# game_console_schematic.net
KiCad netlist of a schematic drawn in Altium Designer
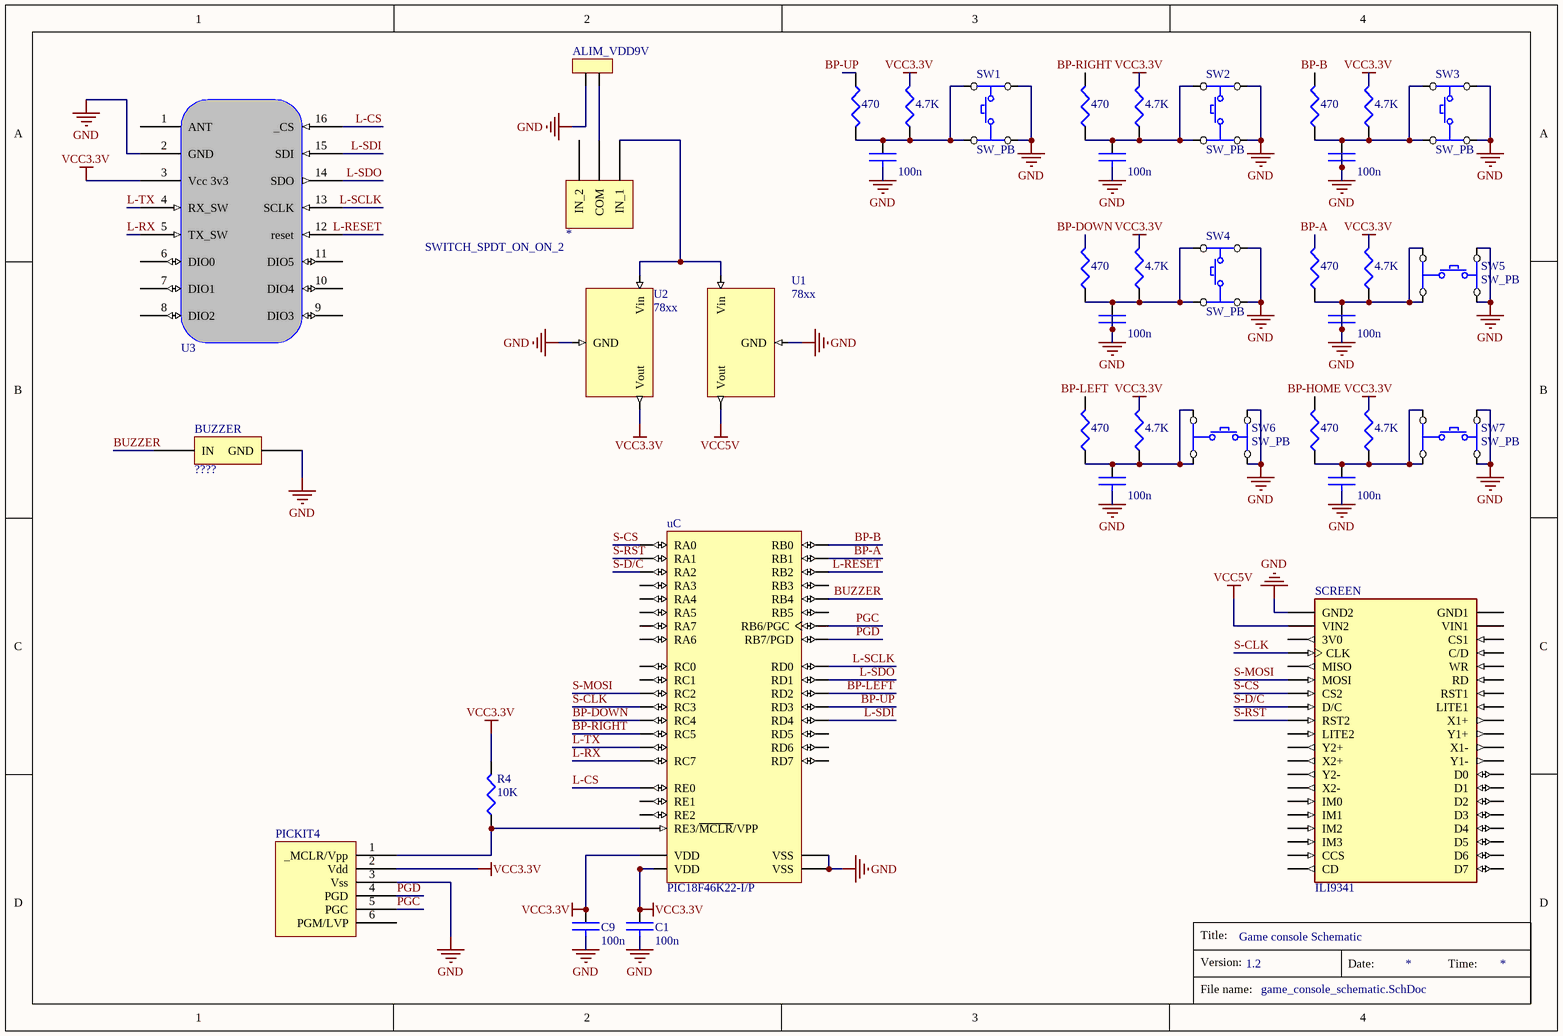
[diagram p0: game_console_schematic.SchDoc]

(export (version "E")
  (design (tool "Eeschema 10.0.6"))
  (components
    (comp (ref "*")
      (value "SWITCH_SPDT_ON_ON_2")
      (footprint "SW_MFP-161")
      (libsource (lib "ISEN_basics_15-02-2023") (part "SWITCH_SPDT_ON_ON_2"))
    )
    (comp (ref "ALIM_VDD9V")
      (value "~")
      (footprint "AMP_2")
      (description "connecteur alim 2 pôles")
      (libsource (lib "ISEN_basics_15-02-2023") (part "POWER2"))
    )
    (comp (ref "BUZZER")
      (value "????")
      (footprint "BUZZER")
      (libsource (lib "ISEN_basics_15-02-2023") (part "BUZZER"))
    )
    (comp (ref "C1")
      (value "100n")
      (footprint "0402")
      (description "capacité non polarisée")
      (fields (field (name "Comment") "CAP"))
      (libsource (lib "ISEN_basics_15-02-2023") (part "CAP"))
    )
    (comp (ref "C2")
      (value "100n")
      (footprint "0402")
      (description "capacité non polarisée")
      (fields (field (name "Comment") "CAP"))
      (libsource (lib "ISEN_basics_15-02-2023") (part "CAP"))
    )
    (comp (ref "C3")
      (value "100n")
      (footprint "0402")
      (description "capacité non polarisée")
      (fields (field (name "Comment") "CAP"))
      (libsource (lib "ISEN_basics_15-02-2023") (part "CAP"))
    )
    (comp (ref "C4")
      (value "100n")
      (footprint "0402")
      (description "capacité non polarisée")
      (fields (field (name "Comment") "CAP"))
      (libsource (lib "ISEN_basics_15-02-2023") (part "CAP"))
    )
    (comp (ref "C5")
      (value "100n")
      (footprint "0402")
      (description "capacité non polarisée")
      (fields (field (name "Comment") "CAP"))
      (libsource (lib "ISEN_basics_15-02-2023") (part "CAP"))
    )
    (comp (ref "C6")
      (value "100n")
      (footprint "0402")
      (description "capacité non polarisée")
      (fields (field (name "Comment") "CAP"))
      (libsource (lib "ISEN_basics_15-02-2023") (part "CAP"))
    )
    (comp (ref "C7")
      (value "100n")
      (footprint "0402")
      (description "capacité non polarisée")
      (fields (field (name "Comment") "CAP"))
      (libsource (lib "ISEN_basics_15-02-2023") (part "CAP"))
    )
    (comp (ref "C8")
      (value "100n")
      (footprint "0402")
      (description "capacité non polarisée")
      (fields (field (name "Comment") "CAP"))
      (libsource (lib "ISEN_basics_15-02-2023") (part "CAP"))
    )
    (comp (ref "C9")
      (value "100n")
      (footprint "0402")
      (description "capacité non polarisée")
      (fields (field (name "Comment") "CAP"))
      (libsource (lib "ISEN_basics_15-02-2023") (part "CAP"))
    )
    (comp (ref "PICKIT4")
      (value "~")
      (footprint "PIC-ICSP")
      (libsource (lib "ISEN_basics_15-02-2023") (part "PIC-ICSP"))
    )
    (comp (ref "R1")
      (value "470")
      (footprint "0201")
      (description "resistance")
      (fields (field (name "Comment") "RES"))
      (libsource (lib "ISEN_basics_15-02-2023") (part "RES"))
    )
    (comp (ref "R2")
      (value "4.7K")
      (footprint "0201")
      (description "resistance")
      (fields (field (name "Comment") "RES"))
      (libsource (lib "ISEN_basics_15-02-2023") (part "RES"))
    )
    (comp (ref "R4")
      (value "10K")
      (footprint "0201")
      (description "resistance")
      (fields (field (name "Comment") "RES"))
      (libsource (lib "ISEN_basics_15-02-2023") (part "RES"))
    )
    (comp (ref "R12")
      (value "470")
      (footprint "0201")
      (description "resistance")
      (fields (field (name "Comment") "RES"))
      (libsource (lib "ISEN_basics_15-02-2023") (part "RES"))
    )
    (comp (ref "R13")
      (value "4.7K")
      (footprint "0201")
      (description "resistance")
      (fields (field (name "Comment") "RES"))
      (libsource (lib "ISEN_basics_15-02-2023") (part "RES"))
    )
    (comp (ref "R14")
      (value "470")
      (footprint "0201")
      (description "resistance")
      (fields (field (name "Comment") "RES"))
      (libsource (lib "ISEN_basics_15-02-2023") (part "RES"))
    )
    (comp (ref "R15")
      (value "4.7K")
      (footprint "0201")
      (description "resistance")
      (fields (field (name "Comment") "RES"))
      (libsource (lib "ISEN_basics_15-02-2023") (part "RES"))
    )
    (comp (ref "R16")
      (value "470")
      (footprint "0201")
      (description "resistance")
      (fields (field (name "Comment") "RES"))
      (libsource (lib "ISEN_basics_15-02-2023") (part "RES"))
    )
    (comp (ref "R17")
      (value "4.7K")
      (footprint "0201")
      (description "resistance")
      (fields (field (name "Comment") "RES"))
      (libsource (lib "ISEN_basics_15-02-2023") (part "RES"))
    )
    (comp (ref "R18")
      (value "470")
      (footprint "0201")
      (description "resistance")
      (fields (field (name "Comment") "RES"))
      (libsource (lib "ISEN_basics_15-02-2023") (part "RES"))
    )
    (comp (ref "R19")
      (value "4.7K")
      (footprint "0201")
      (description "resistance")
      (fields (field (name "Comment") "RES"))
      (libsource (lib "ISEN_basics_15-02-2023") (part "RES"))
    )
    (comp (ref "R20")
      (value "470")
      (footprint "0201")
      (description "resistance")
      (fields (field (name "Comment") "RES"))
      (libsource (lib "ISEN_basics_15-02-2023") (part "RES"))
    )
    (comp (ref "R21")
      (value "4.7K")
      (footprint "0201")
      (description "resistance")
      (fields (field (name "Comment") "RES"))
      (libsource (lib "ISEN_basics_15-02-2023") (part "RES"))
    )
    (comp (ref "R22")
      (value "470")
      (footprint "0201")
      (description "resistance")
      (fields (field (name "Comment") "RES"))
      (libsource (lib "ISEN_basics_15-02-2023") (part "RES"))
    )
    (comp (ref "R23")
      (value "4.7K")
      (footprint "0201")
      (description "resistance")
      (fields (field (name "Comment") "RES"))
      (libsource (lib "ISEN_basics_15-02-2023") (part "RES"))
    )
    (comp (ref "SCREEN")
      (value "ILI9341")
      (footprint "ADAFRUIT_2478")
      (fields (field (name "MF") "Adafruit Industries") (field (name "MP") "2478"))
      (libsource (lib "2478") (part "2478"))
    )
    (comp (ref "SW1") (value "SW_PB") (footprint "KSA") (libsource (lib "custom_push_button") (part "SW_PB")))
    (comp (ref "SW2") (value "SW_PB") (footprint "KSA") (libsource (lib "custom_push_button") (part "SW_PB")))
    (comp (ref "SW3") (value "SW_PB") (footprint "KSA") (libsource (lib "custom_push_button") (part "SW_PB")))
    (comp (ref "SW4") (value "SW_PB") (footprint "KSA") (libsource (lib "custom_push_button") (part "SW_PB")))
    (comp (ref "SW5") (value "SW_PB") (footprint "KSA") (libsource (lib "custom_push_button") (part "SW_PB")))
    (comp (ref "SW6") (value "SW_PB") (footprint "KSA") (libsource (lib "custom_push_button") (part "SW_PB")))
    (comp (ref "SW7") (value "SW_PB") (footprint "KSA") (libsource (lib "custom_push_button") (part "SW_PB")))
    (comp (ref "U1")
      (value "78xx")
      (footprint "TO220H")
      (description "régulateur positif fixe")
      (libsource (lib "ISEN_basics_15-02-2023") (part "REG_POS"))
    )
    (comp (ref "U2")
      (value "78xx")
      (footprint "TO220H")
      (description "régulateur positif fixe")
      (libsource (lib "") (part "REG_POS_1"))
    )
    (comp (ref "U3")
      (value "RF-LORA-868-SO")
      (footprint "RF-LORA-868-DIP")
      (libsource (lib "ISEN_basics_15-02-2023") (part "RF-LORA-868-SO"))
    )
    (comp (ref "uC")
      (value "PIC18F46K22-I/P")
      (footprint "MCHP-PDIP-P40")
      (fields (field (name "MANUFACTURER") "Microchip"))
      (libsource (lib "Microchip PIC18") (part "PIC18F46K22-I/P"))
    )
  )
  (nets
    (net (code "1") (name "/BP-A") (class "Default")
      (node (ref "R22") (pin "2") (pintype "passive"))
      (node (ref "uC") (pin "34") (pinfunction "RB1_34") (pintype "bidirectional"))
    )
    (net (code "2") (name "/BP-B") (class "Default")
      (node (ref "R16") (pin "2") (pintype "passive"))
      (node (ref "uC") (pin "33") (pinfunction "RB0_33") (pintype "bidirectional"))
    )
    (net (code "3") (name "/BP-DOWN") (class "Default")
      (node (ref "R20") (pin "2") (pintype "passive"))
      (node (ref "uC") (pin "23") (pinfunction "RC4_23") (pintype "bidirectional"))
    )
    (net (code "4") (name "/BP-HOME") (class "Default") (node (ref "R1") (pin "2") (pintype "passive")))
    (net (code "5") (name "/BP-LEFT") (class "Default")
      (node (ref "R18") (pin "2") (pintype "passive"))
      (node (ref "uC") (pin "21") (pinfunction "RD2_21") (pintype "bidirectional"))
    )
    (net (code "6") (name "/BP-RIGHT") (class "Default")
      (node (ref "R14") (pin "2") (pintype "passive"))
      (node (ref "uC") (pin "24") (pinfunction "RC5_24") (pintype "bidirectional"))
    )
    (net (code "7") (name "/BP-UP") (class "Default")
      (node (ref "R12") (pin "1") (pintype "passive"))
      (node (ref "uC") (pin "22") (pinfunction "RD3_22") (pintype "bidirectional"))
    )
    (net (code "8") (name "/BUZZER") (class "Default")
      (node (ref "BUZZER") (pin "1") (pinfunction "IN_1") (pintype "passive"))
      (node (ref "uC") (pin "37") (pinfunction "RB4_37") (pintype "bidirectional"))
    )
    (net (code "9") (name "/L-CS") (class "Default")
      (node (ref "U3") (pin "16") (pinfunction "_CS_16") (pintype "input"))
      (node (ref "uC") (pin "8") (pinfunction "RE0_8") (pintype "bidirectional"))
    )
    (net (code "10") (name "/L-RESET") (class "Default")
      (node (ref "U3") (pin "12") (pinfunction "reset_12") (pintype "input"))
      (node (ref "uC") (pin "35") (pinfunction "RB2_35") (pintype "bidirectional"))
    )
    (net (code "11") (name "/L-RX") (class "Default")
      (node (ref "U3") (pin "5") (pinfunction "TX_SW_5") (pintype "input"))
      (node (ref "uC") (pin "26") (pinfunction "RC7_26") (pintype "bidirectional"))
    )
    (net (code "12") (name "/L-SCLK") (class "Default")
      (node (ref "U3") (pin "13") (pinfunction "SCLK_13") (pintype "input"))
      (node (ref "uC") (pin "19") (pinfunction "RD0_19") (pintype "bidirectional"))
    )
    (net (code "13") (name "/L-SDI") (class "Default")
      (node (ref "U3") (pin "15") (pinfunction "SDI_15") (pintype "input"))
      (node (ref "uC") (pin "27") (pinfunction "RD4_27") (pintype "bidirectional"))
    )
    (net (code "14") (name "/L-SDO") (class "Default")
      (node (ref "U3") (pin "14") (pinfunction "SDO_14") (pintype "output"))
      (node (ref "uC") (pin "20") (pinfunction "RD1_20") (pintype "bidirectional"))
    )
    (net (code "15") (name "/L-TX") (class "Default")
      (node (ref "U3") (pin "4") (pinfunction "RX_SW_4") (pintype "input"))
      (node (ref "uC") (pin "25") (pinfunction "RC6_25") (pintype "bidirectional"))
    )
    (net (code "16") (name "/PGC") (class "Default")
      (node (ref "PICKIT4") (pin "5") (pinfunction "PGC_5") (pintype "passive"))
      (node (ref "uC") (pin "39") (pinfunction "RB6/PGC_39") (pintype "bidirectional"))
    )
    (net (code "17") (name "/PGD") (class "Default")
      (node (ref "PICKIT4") (pin "4") (pinfunction "PGD_4") (pintype "passive"))
      (node (ref "uC") (pin "40") (pinfunction "RB7/PGD_40") (pintype "bidirectional"))
    )
    (net (code "18") (name "/S-CLK") (class "Default")
      (node (ref "SCREEN") (pin "24") (pinfunction "CLK_24") (pintype "input"))
      (node (ref "uC") (pin "18") (pinfunction "RC3_18") (pintype "bidirectional"))
    )
    (net (code "19") (name "/S-CS") (class "Default")
      (node (ref "SCREEN") (pin "27") (pinfunction "CS2_27") (pintype "input"))
      (node (ref "uC") (pin "2") (pinfunction "RA0_2") (pintype "bidirectional"))
    )
    (net (code "20") (name "/S-D{slash}C") (class "Default")
      (node (ref "SCREEN") (pin "28") (pinfunction "D/C_28") (pintype "input"))
      (node (ref "uC") (pin "4") (pinfunction "RA2_4") (pintype "bidirectional"))
    )
    (net (code "21") (name "/S-MOSI") (class "Default")
      (node (ref "SCREEN") (pin "26") (pinfunction "MOSI_26") (pintype "input"))
      (node (ref "uC") (pin "17") (pinfunction "RC2_17") (pintype "bidirectional"))
    )
    (net (code "22") (name "/S-RST") (class "Default")
      (node (ref "SCREEN") (pin "29") (pinfunction "RST2_29") (pintype "input"))
      (node (ref "uC") (pin "3") (pinfunction "RA1_3") (pintype "bidirectional"))
    )
    (net (code "23") (name "GND") (class "Default")
      (node (ref "ALIM_VDD9V") (pin "2") (pintype "passive"))
      (node (ref "BUZZER") (pin "2") (pinfunction "GND_2") (pintype "passive"))
      (node (ref "C1") (pin "2") (pinfunction "2_2") (pintype "passive"))
      (node (ref "C2") (pin "2") (pinfunction "2_2") (pintype "passive"))
      (node (ref "C3") (pin "2") (pinfunction "2_2") (pintype "passive"))
      (node (ref "C4") (pin "2") (pinfunction "2_2") (pintype "passive"))
      (node (ref "C5") (pin "2") (pinfunction "2_2") (pintype "passive"))
      (node (ref "C6") (pin "2") (pinfunction "2_2") (pintype "passive"))
      (node (ref "C7") (pin "2") (pinfunction "2_2") (pintype "passive"))
      (node (ref "C8") (pin "2") (pinfunction "2_2") (pintype "passive"))
      (node (ref "C9") (pin "2") (pinfunction "2_2") (pintype "passive"))
      (node (ref "PICKIT4") (pin "3") (pinfunction "Vss_3") (pintype "passive"))
      (node (ref "SCREEN") (pin "21") (pinfunction "GND2_21") (pintype "power_in"))
      (node (ref "SW1") (pin "2") (pintype "passive"))
      (node (ref "SW1") (pin "4") (pintype "passive"))
      (node (ref "SW2") (pin "2") (pintype "passive"))
      (node (ref "SW2") (pin "4") (pintype "passive"))
      (node (ref "SW3") (pin "2") (pintype "passive"))
      (node (ref "SW3") (pin "4") (pintype "passive"))
      (node (ref "SW4") (pin "2") (pintype "passive"))
      (node (ref "SW4") (pin "4") (pintype "passive"))
      (node (ref "SW5") (pin "3") (pintype "passive"))
      (node (ref "SW5") (pin "4") (pintype "passive"))
      (node (ref "SW6") (pin "3") (pintype "passive"))
      (node (ref "SW6") (pin "4") (pintype "passive"))
      (node (ref "SW7") (pin "3") (pintype "passive"))
      (node (ref "SW7") (pin "4") (pintype "passive"))
      (node (ref "U1") (pin "2") (pinfunction "GND_2") (pintype "input"))
      (node (ref "U2") (pin "2") (pinfunction "GND_2") (pintype "input"))
      (node (ref "U3") (pin "2") (pinfunction "GND_2") (pintype "power_in"))
      (node (ref "uC") (pin "12") (pinfunction "VSS_12") (pintype "power_in"))
      (node (ref "uC") (pin "31") (pinfunction "VSS_31") (pintype "power_in"))
    )
    (net (code "24") (name "Net-(*-COM)") (class "Default")
      (node (ref "*") (pin "2") (pinfunction "COM_2") (pintype "passive"))
      (node (ref "ALIM_VDD9V") (pin "1") (pintype "passive"))
    )
    (net (code "25") (name "Net-(*-IN_1)") (class "Default")
      (node (ref "*") (pin "1") (pinfunction "IN_1_1") (pintype "passive"))
      (node (ref "U1") (pin "1") (pinfunction "Vin_1") (pintype "input"))
      (node (ref "U2") (pin "1") (pinfunction "Vin_1") (pintype "input"))
    )
    (net (code "26") (name "Net-(C2-Pad1)") (class "Default")
      (node (ref "C2") (pin "1") (pinfunction "1_1") (pintype "passive"))
      (node (ref "R12") (pin "2") (pintype "passive"))
      (node (ref "R13") (pin "1") (pintype "passive"))
      (node (ref "SW1") (pin "1") (pintype "passive"))
      (node (ref "SW1") (pin "3") (pintype "passive"))
    )
    (net (code "27") (name "Net-(C3-Pad1)") (class "Default")
      (node (ref "C3") (pin "1") (pinfunction "1_1") (pintype "passive"))
      (node (ref "R14") (pin "1") (pintype "passive"))
      (node (ref "R15") (pin "1") (pintype "passive"))
      (node (ref "SW2") (pin "1") (pintype "passive"))
      (node (ref "SW2") (pin "3") (pintype "passive"))
    )
    (net (code "28") (name "Net-(C4-Pad1)") (class "Default")
      (node (ref "C4") (pin "1") (pinfunction "1_1") (pintype "passive"))
      (node (ref "R16") (pin "1") (pintype "passive"))
      (node (ref "R17") (pin "1") (pintype "passive"))
      (node (ref "SW3") (pin "1") (pintype "passive"))
      (node (ref "SW3") (pin "3") (pintype "passive"))
    )
    (net (code "29") (name "Net-(C5-Pad1)") (class "Default")
      (node (ref "C5") (pin "1") (pinfunction "1_1") (pintype "passive"))
      (node (ref "R18") (pin "1") (pintype "passive"))
      (node (ref "R19") (pin "1") (pintype "passive"))
      (node (ref "SW6") (pin "1") (pintype "passive"))
      (node (ref "SW6") (pin "2") (pintype "passive"))
    )
    (net (code "30") (name "Net-(C6-Pad1)") (class "Default")
      (node (ref "C6") (pin "1") (pinfunction "1_1") (pintype "passive"))
      (node (ref "R20") (pin "1") (pintype "passive"))
      (node (ref "R21") (pin "1") (pintype "passive"))
      (node (ref "SW4") (pin "1") (pintype "passive"))
      (node (ref "SW4") (pin "3") (pintype "passive"))
    )
    (net (code "31") (name "Net-(C7-Pad1)") (class "Default")
      (node (ref "C7") (pin "1") (pinfunction "1_1") (pintype "passive"))
      (node (ref "R22") (pin "1") (pintype "passive"))
      (node (ref "R23") (pin "1") (pintype "passive"))
      (node (ref "SW5") (pin "1") (pintype "passive"))
      (node (ref "SW5") (pin "2") (pintype "passive"))
    )
    (net (code "32") (name "Net-(C8-Pad1)") (class "Default")
      (node (ref "C8") (pin "1") (pinfunction "1_1") (pintype "passive"))
      (node (ref "R1") (pin "1") (pintype "passive"))
      (node (ref "R2") (pin "1") (pintype "passive"))
      (node (ref "SW7") (pin "1") (pintype "passive"))
      (node (ref "SW7") (pin "2") (pintype "passive"))
    )
    (net (code "33") (name "Net-(PICKIT4-_MCLR{slash}Vpp)") (class "Default")
      (node (ref "PICKIT4") (pin "1") (pinfunction "_MCLR/Vpp_1") (pintype "passive"))
      (node (ref "R4") (pin "1") (pintype "passive"))
      (node (ref "uC") (pin "1") (pinfunction "RE3/~{MCLR}/VPP_1") (pintype "input"))
    )
    (net (code "34") (name "VCC3.3V") (class "Default")
      (node (ref "C1") (pin "1") (pinfunction "1_1") (pintype "passive"))
      (node (ref "C9") (pin "1") (pinfunction "1_1") (pintype "passive"))
      (node (ref "PICKIT4") (pin "2") (pinfunction "Vdd_2") (pintype "passive"))
      (node (ref "R13") (pin "2") (pintype "passive"))
      (node (ref "R15") (pin "2") (pintype "passive"))
      (node (ref "R17") (pin "2") (pintype "passive"))
      (node (ref "R19") (pin "2") (pintype "passive"))
      (node (ref "R2") (pin "2") (pintype "passive"))
      (node (ref "R21") (pin "2") (pintype "passive"))
      (node (ref "R23") (pin "2") (pintype "passive"))
      (node (ref "R4") (pin "2") (pintype "passive"))
      (node (ref "U2") (pin "3") (pinfunction "Vout_3") (pintype "output"))
      (node (ref "U3") (pin "3") (pinfunction "Vcc_3v3_3") (pintype "power_in"))
      (node (ref "uC") (pin "11") (pinfunction "VDD_11") (pintype "power_in"))
      (node (ref "uC") (pin "32") (pinfunction "VDD_32") (pintype "power_in"))
    )
    (net (code "35") (name "VCC5V") (class "Default")
      (node (ref "SCREEN") (pin "22") (pinfunction "VIN2_22") (pintype "power_in"))
      (node (ref "U1") (pin "3") (pinfunction "Vout_3") (pintype "output"))
    )
    (net (code "36") (name "unconnected-(*-IN_2-Pad3)") (class "Default")
      (node (ref "*") (pin "3") (pinfunction "IN_2_3") (pintype "passive"))
    )
    (net (code "37") (name "unconnected-(PICKIT4-PGM{slash}LVP-Pad6)") (class "Default")
      (node (ref "PICKIT4") (pin "6") (pinfunction "PGM/LVP_6") (pintype "passive"))
    )
    (net (code "38") (name "unconnected-(SCREEN-3V0-Pad23)") (class "Default")
      (node (ref "SCREEN") (pin "23") (pinfunction "3V0_23") (pintype "output"))
    )
    (net (code "39") (name "unconnected-(SCREEN-CCS-Pad39)") (class "Default")
      (node (ref "SCREEN") (pin "39") (pinfunction "CCS_39") (pintype "input"))
    )
    (net (code "40") (name "unconnected-(SCREEN-CD-Pad40)") (class "Default")
      (node (ref "SCREEN") (pin "40") (pinfunction "CD_40") (pintype "output"))
    )
    (net (code "41") (name "unconnected-(SCREEN-CS1-Pad3)") (class "Default")
      (node (ref "SCREEN") (pin "3") (pinfunction "CS1_3") (pintype "input"))
    )
    (net (code "42") (name "unconnected-(SCREEN-C{slash}D-Pad4)") (class "Default")
      (node (ref "SCREEN") (pin "4") (pinfunction "C/D_4") (pintype "input"))
    )
    (net (code "43") (name "unconnected-(SCREEN-D0-Pad13)") (class "Default")
      (node (ref "SCREEN") (pin "13") (pinfunction "D0_13") (pintype "bidirectional"))
    )
    (net (code "44") (name "unconnected-(SCREEN-D1-Pad14)") (class "Default")
      (node (ref "SCREEN") (pin "14") (pinfunction "D1_14") (pintype "bidirectional"))
    )
    (net (code "45") (name "unconnected-(SCREEN-D2-Pad15)") (class "Default")
      (node (ref "SCREEN") (pin "15") (pinfunction "D2_15") (pintype "bidirectional"))
    )
    (net (code "46") (name "unconnected-(SCREEN-D3-Pad16)") (class "Default")
      (node (ref "SCREEN") (pin "16") (pinfunction "D3_16") (pintype "bidirectional"))
    )
    (net (code "47") (name "unconnected-(SCREEN-D4-Pad17)") (class "Default")
      (node (ref "SCREEN") (pin "17") (pinfunction "D4_17") (pintype "bidirectional"))
    )
    (net (code "48") (name "unconnected-(SCREEN-D5-Pad18)") (class "Default")
      (node (ref "SCREEN") (pin "18") (pinfunction "D5_18") (pintype "bidirectional"))
    )
    (net (code "49") (name "unconnected-(SCREEN-D6-Pad19)") (class "Default")
      (node (ref "SCREEN") (pin "19") (pinfunction "D6_19") (pintype "bidirectional"))
    )
    (net (code "50") (name "unconnected-(SCREEN-D7-Pad20)") (class "Default")
      (node (ref "SCREEN") (pin "20") (pinfunction "D7_20") (pintype "bidirectional"))
    )
    (net (code "51") (name "unconnected-(SCREEN-GND1-Pad1)") (class "Default")
      (node (ref "SCREEN") (pin "1") (pinfunction "GND1_1") (pintype "power_in"))
    )
    (net (code "52") (name "unconnected-(SCREEN-IM0-Pad35)") (class "Default")
      (node (ref "SCREEN") (pin "35") (pinfunction "IM0_35") (pintype "input"))
    )
    (net (code "53") (name "unconnected-(SCREEN-IM1-Pad36)") (class "Default")
      (node (ref "SCREEN") (pin "36") (pinfunction "IM1_36") (pintype "input"))
    )
    (net (code "54") (name "unconnected-(SCREEN-IM2-Pad37)") (class "Default")
      (node (ref "SCREEN") (pin "37") (pinfunction "IM2_37") (pintype "input"))
    )
    (net (code "55") (name "unconnected-(SCREEN-IM3-Pad38)") (class "Default")
      (node (ref "SCREEN") (pin "38") (pinfunction "IM3_38") (pintype "input"))
    )
    (net (code "56") (name "unconnected-(SCREEN-LITE1-Pad8)") (class "Default")
      (node (ref "SCREEN") (pin "8") (pinfunction "LITE1_8") (pintype "input"))
    )
    (net (code "57") (name "unconnected-(SCREEN-LITE2-Pad30)") (class "Default")
      (node (ref "SCREEN") (pin "30") (pinfunction "LITE2_30") (pintype "input"))
    )
    (net (code "58") (name "unconnected-(SCREEN-MISO-Pad25)") (class "Default")
      (node (ref "SCREEN") (pin "25") (pinfunction "MISO_25") (pintype "output"))
    )
    (net (code "59") (name "unconnected-(SCREEN-RD-Pad6)") (class "Default")
      (node (ref "SCREEN") (pin "6") (pinfunction "RD_6") (pintype "input"))
    )
    (net (code "60") (name "unconnected-(SCREEN-RST1-Pad7)") (class "Default")
      (node (ref "SCREEN") (pin "7") (pinfunction "RST1_7") (pintype "input"))
    )
    (net (code "61") (name "unconnected-(SCREEN-VIN1-Pad2)") (class "Default")
      (node (ref "SCREEN") (pin "2") (pinfunction "VIN1_2") (pintype "power_in"))
    )
    (net (code "62") (name "unconnected-(SCREEN-WR-Pad5)") (class "Default")
      (node (ref "SCREEN") (pin "5") (pinfunction "WR_5") (pintype "input"))
    )
    (net (code "63") (name "unconnected-(SCREEN-X1+-Pad9)") (class "Default")
      (node (ref "SCREEN") (pin "9") (pinfunction "X1+_9") (pintype "output"))
    )
    (net (code "64") (name "unconnected-(SCREEN-X1--Pad11)") (class "Default")
      (node (ref "SCREEN") (pin "11") (pinfunction "X1-_11") (pintype "output"))
    )
    (net (code "65") (name "unconnected-(SCREEN-X2+-Pad32)") (class "Default")
      (node (ref "SCREEN") (pin "32") (pinfunction "X2+_32") (pintype "output"))
    )
    (net (code "66") (name "unconnected-(SCREEN-X2--Pad34)") (class "Default")
      (node (ref "SCREEN") (pin "34") (pinfunction "X2-_34") (pintype "output"))
    )
    (net (code "67") (name "unconnected-(SCREEN-Y1+-Pad10)") (class "Default")
      (node (ref "SCREEN") (pin "10") (pinfunction "Y1+_10") (pintype "output"))
    )
    (net (code "68") (name "unconnected-(SCREEN-Y1--Pad12)") (class "Default")
      (node (ref "SCREEN") (pin "12") (pinfunction "Y1-_12") (pintype "output"))
    )
    (net (code "69") (name "unconnected-(SCREEN-Y2+-Pad31)") (class "Default")
      (node (ref "SCREEN") (pin "31") (pinfunction "Y2+_31") (pintype "output"))
    )
    (net (code "70") (name "unconnected-(SCREEN-Y2--Pad33)") (class "Default")
      (node (ref "SCREEN") (pin "33") (pinfunction "Y2-_33") (pintype "output"))
    )
    (net (code "71") (name "unconnected-(U3-ANT-Pad1)") (class "Default")
      (node (ref "U3") (pin "1") (pinfunction "ANT_1") (pintype "passive"))
    )
    (net (code "72") (name "unconnected-(U3-DIO0-Pad6)") (class "Default")
      (node (ref "U3") (pin "6") (pinfunction "DIO0_6") (pintype "bidirectional"))
    )
    (net (code "73") (name "unconnected-(U3-DIO1-Pad7)") (class "Default")
      (node (ref "U3") (pin "7") (pinfunction "DIO1_7") (pintype "bidirectional"))
    )
    (net (code "74") (name "unconnected-(U3-DIO2-Pad8)") (class "Default")
      (node (ref "U3") (pin "8") (pinfunction "DIO2_8") (pintype "bidirectional"))
    )
    (net (code "75") (name "unconnected-(U3-DIO3-Pad9)") (class "Default")
      (node (ref "U3") (pin "9") (pinfunction "DIO3_9") (pintype "bidirectional"))
    )
    (net (code "76") (name "unconnected-(U3-DIO4-Pad10)") (class "Default")
      (node (ref "U3") (pin "10") (pinfunction "DIO4_10") (pintype "bidirectional"))
    )
    (net (code "77") (name "unconnected-(U3-DIO5-Pad11)") (class "Default")
      (node (ref "U3") (pin "11") (pinfunction "DIO5_11") (pintype "bidirectional"))
    )
    (net (code "78") (name "unconnected-(uC-RA3-Pad5)") (class "Default")
      (node (ref "uC") (pin "5") (pinfunction "RA3_5") (pintype "bidirectional"))
    )
    (net (code "79") (name "unconnected-(uC-RA4-Pad6)") (class "Default")
      (node (ref "uC") (pin "6") (pinfunction "RA4_6") (pintype "bidirectional"))
    )
    (net (code "80") (name "unconnected-(uC-RA5-Pad7)") (class "Default")
      (node (ref "uC") (pin "7") (pinfunction "RA5_7") (pintype "bidirectional"))
    )
    (net (code "81") (name "unconnected-(uC-RA6-Pad14)") (class "Default")
      (node (ref "uC") (pin "14") (pinfunction "RA6_14") (pintype "bidirectional"))
    )
    (net (code "82") (name "unconnected-(uC-RA7-Pad13)") (class "Default")
      (node (ref "uC") (pin "13") (pinfunction "RA7_13") (pintype "bidirectional"))
    )
    (net (code "83") (name "unconnected-(uC-RB3-Pad36)") (class "Default")
      (node (ref "uC") (pin "36") (pinfunction "RB3_36") (pintype "bidirectional"))
    )
    (net (code "84") (name "unconnected-(uC-RB5-Pad38)") (class "Default")
      (node (ref "uC") (pin "38") (pinfunction "RB5_38") (pintype "bidirectional"))
    )
    (net (code "85") (name "unconnected-(uC-RC0-Pad15)") (class "Default")
      (node (ref "uC") (pin "15") (pinfunction "RC0_15") (pintype "bidirectional"))
    )
    (net (code "86") (name "unconnected-(uC-RC1-Pad16)") (class "Default")
      (node (ref "uC") (pin "16") (pinfunction "RC1_16") (pintype "bidirectional"))
    )
    (net (code "87") (name "unconnected-(uC-RD5-Pad28)") (class "Default")
      (node (ref "uC") (pin "28") (pinfunction "RD5_28") (pintype "bidirectional"))
    )
    (net (code "88") (name "unconnected-(uC-RD6-Pad29)") (class "Default")
      (node (ref "uC") (pin "29") (pinfunction "RD6_29") (pintype "bidirectional"))
    )
    (net (code "89") (name "unconnected-(uC-RD7-Pad30)") (class "Default")
      (node (ref "uC") (pin "30") (pinfunction "RD7_30") (pintype "bidirectional"))
    )
    (net (code "90") (name "unconnected-(uC-RE1-Pad9)") (class "Default")
      (node (ref "uC") (pin "9") (pinfunction "RE1_9") (pintype "bidirectional"))
    )
    (net (code "91") (name "unconnected-(uC-RE2-Pad10)") (class "Default")
      (node (ref "uC") (pin "10") (pinfunction "RE2_10") (pintype "bidirectional"))
    )
  )
)
